# 04_USB.net
KiCad netlist of a schematic drawn in Altium Designer
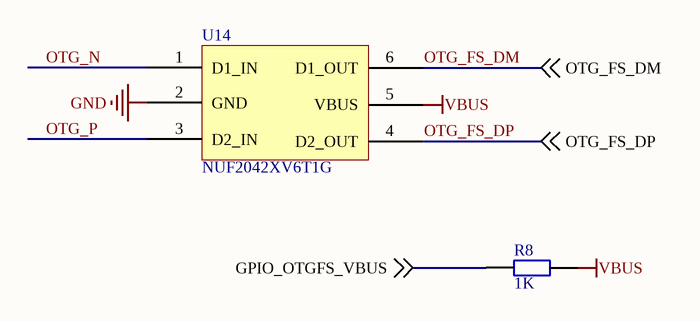
[diagram p0: 04_USB.SchDoc]

(export (version "E")
  (design (tool "Eeschema 10.0.6"))
  (components
    (comp (ref "R8")
      (value "1K")
      (footprint "0402R")
      (description "0402R10K 1%")
      (libsource (lib "CUAV") (part "0402R10K"))
    )
    (comp (ref "U14")
      (value "NUF2042XV6T1G")
      (footprint "SOT563-6")
      (libsource (lib "hack") (part "NUF2042XV6T1G"))
    )
  )
  (nets
    (net (code "1") (name "/OTG_N") (class "Default")
      (node (ref "U14") (pin "1") (pinfunction "D1_IN_1") (pintype "passive"))
    )
    (net (code "2") (name "/OTG_P") (class "Default")
      (node (ref "U14") (pin "3") (pinfunction "D2_IN_3") (pintype "passive"))
    )
    (net (code "3") (name "GND") (class "Default")
      (node (ref "U14") (pin "2") (pinfunction "GND_2") (pintype "passive"))
    )
    (net (code "4") (name "GPIO_OTGFS_VBUS") (class "Default")
      (node (ref "R8") (pin "1") (pintype "passive"))
    )
    (net (code "5") (name "OTG_FS_DM") (class "Default")
      (node (ref "U14") (pin "6") (pinfunction "D1_OUT_6") (pintype "passive"))
    )
    (net (code "6") (name "OTG_FS_DP") (class "Default")
      (node (ref "U14") (pin "4") (pinfunction "D2_OUT_4") (pintype "passive"))
    )
    (net (code "7") (name "VBUS") (class "Default")
      (node (ref "R8") (pin "2") (pintype "passive"))
      (node (ref "U14") (pin "5") (pinfunction "VBUS_5") (pintype "passive"))
    )
  )
)
